# speed_control.net
KiCad netlist of a schematic drawn in EAGLE
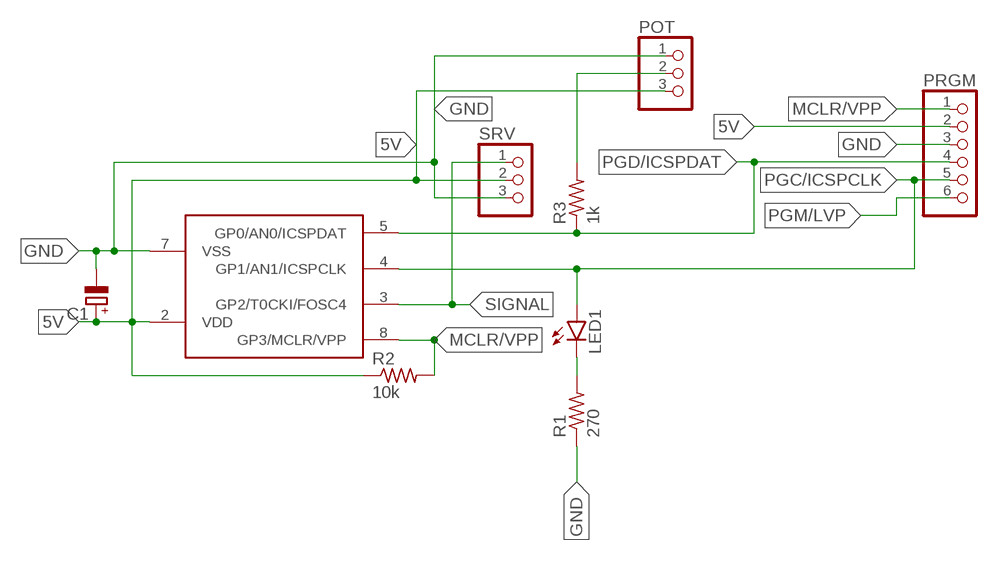
[diagram p0: schematic, sheet 1]

(export (version "E")
  (design (tool "Eeschema 10.0.6"))
  (components
    (comp (ref "C1")
      (value "CPOL-EUE3.5-8")
      (footprint "eagle-import:E3,5-8")
      (libsource (lib "eagle-import") (part "CPOL-EUE3.5-8"))
    )
    (comp (ref "LED1")
      (value "LED3MM")
      (footprint "eagle-import:LED3MM")
      (libsource (lib "eagle-import") (part "LED3MM"))
    )
    (comp (ref "POT")
      (value "PINHD-1X3")
      (footprint "eagle-import:1X03")
      (libsource (lib "eagle-import") (part "PINHD-1X3"))
    )
    (comp (ref "PRGM")
      (value "PINHD-1X6")
      (footprint "eagle-import:1X06")
      (libsource (lib "eagle-import") (part "PINHD-1X6"))
    )
    (comp (ref "R1")
      (value "270")
      (footprint "eagle-import:0207_10")
      (libsource (lib "eagle-import") (part "R-US_0207/10"))
    )
    (comp (ref "R2")
      (value "10k")
      (footprint "eagle-import:0207_10")
      (libsource (lib "eagle-import") (part "R-US_0207/10"))
    )
    (comp (ref "R3")
      (value "1k")
      (footprint "eagle-import:0207_10")
      (libsource (lib "eagle-import") (part "R-US_0207/10"))
    )
    (comp (ref "SRV")
      (value "PINHD-1X3/90")
      (footprint "eagle-import:1X03_90")
      (libsource (lib "eagle-import") (part "PINHD-1X3/90"))
    )
    (comp (ref "U$1")
      (value "PIC10F222PIC10F222")
      (footprint "eagle-import:DIP762W53P254L955H330Q8B")
      (libsource (lib "eagle-import") (part "PIC10F222PIC10F222"))
    )
  )
  (nets
    (net (code "1") (name "5V") (class "Default")
      (node (ref "C1") (pin "+") (pinfunction "+_+") (pintype "passive"))
      (node (ref "POT") (pin "3") (pinfunction "3_3") (pintype "passive"))
      (node (ref "PRGM") (pin "2") (pinfunction "2_2") (pintype "passive"))
      (node (ref "R2") (pin "1") (pinfunction "1_1") (pintype "passive"))
      (node (ref "SRV") (pin "2") (pinfunction "2_2") (pintype "passive"))
      (node (ref "U$1") (pin "2") (pinfunction "VDD_2") (pintype "bidirectional"))
    )
    (net (code "2") (name "GND") (class "Default")
      (node (ref "C1") (pin "-") (pinfunction "-_-") (pintype "passive"))
      (node (ref "POT") (pin "1") (pinfunction "1_1") (pintype "passive"))
      (node (ref "PRGM") (pin "3") (pinfunction "3_3") (pintype "passive"))
      (node (ref "R1") (pin "1") (pinfunction "1_1") (pintype "passive"))
      (node (ref "SRV") (pin "3") (pinfunction "3_3") (pintype "passive"))
      (node (ref "U$1") (pin "7") (pinfunction "VSS_7") (pintype "bidirectional"))
    )
    (net (code "3") (name "MCLR{slash}VPP") (class "Default")
      (node (ref "PRGM") (pin "1") (pinfunction "1_1") (pintype "passive"))
      (node (ref "R2") (pin "2") (pinfunction "2_2") (pintype "passive"))
      (node (ref "U$1") (pin "8") (pinfunction "GP3/MCLR/VPP_8") (pintype "bidirectional"))
    )
    (net (code "4") (name "Net-(LED1-C)") (class "Default")
      (node (ref "LED1") (pin "K") (pinfunction "C_K") (pintype "passive"))
      (node (ref "R1") (pin "2") (pinfunction "2_2") (pintype "passive"))
    )
    (net (code "5") (name "Net-(POT-Pad2)") (class "Default")
      (node (ref "POT") (pin "2") (pinfunction "2_2") (pintype "passive"))
      (node (ref "R3") (pin "2") (pinfunction "2_2") (pintype "passive"))
    )
    (net (code "6") (name "PGC{slash}ICSPCLK") (class "Default")
      (node (ref "LED1") (pin "A") (pinfunction "A_A") (pintype "passive"))
      (node (ref "PRGM") (pin "5") (pinfunction "5_5") (pintype "passive"))
      (node (ref "U$1") (pin "4") (pinfunction "GP1/AN1/ICSPCLK_4") (pintype "bidirectional"))
    )
    (net (code "7") (name "PGD{slash}ICSPDAT") (class "Default")
      (node (ref "PRGM") (pin "4") (pinfunction "4_4") (pintype "passive"))
      (node (ref "R3") (pin "1") (pinfunction "1_1") (pintype "passive"))
      (node (ref "U$1") (pin "5") (pinfunction "GP0/AN0/ICSPDAT_5") (pintype "bidirectional"))
    )
    (net (code "8") (name "PGM{slash}LVP") (class "Default")
      (node (ref "PRGM") (pin "6") (pinfunction "6_6") (pintype "passive"))
    )
    (net (code "9") (name "SIGNAL") (class "Default")
      (node (ref "SRV") (pin "1") (pinfunction "1_1") (pintype "passive"))
      (node (ref "U$1") (pin "3") (pinfunction "GP2/T0CKI/FOSC4_3") (pintype "bidirectional"))
    )
  )
)
